# UWB_5V-3V3_LDO.net
KiCad netlist of a schematic drawn in Altium Designer
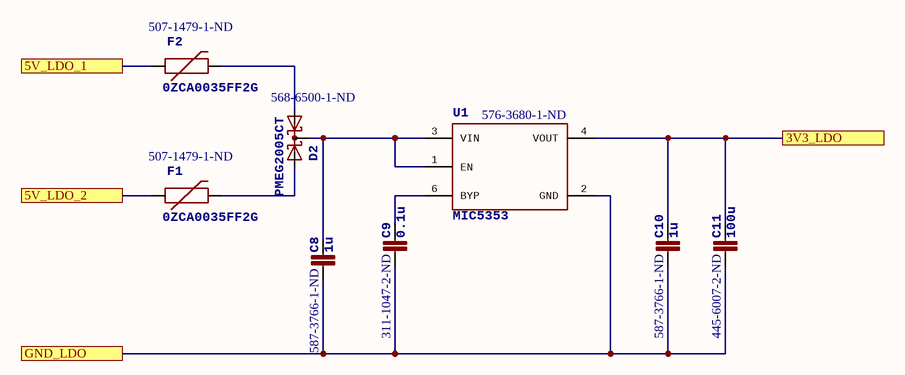
[diagram p0: UWB_5V-3V3_LDO.SchDoc]

(export (version "E")
  (design (tool "Eeschema 10.0.6"))
  (components
    (comp (ref "C8")
      (value "1u")
      (footprint "0603-CAP")
      (fields
        (field (name "PARTNO") "LMK107B7105KA-T")
        (field (name "SUPPLIER PART NUMBER 1") "587-3766-1-ND")
      )
      (libsource (lib "altium-import") (part "root_0_CAPACITOR-0603_"))
    )
    (comp (ref "C9")
      (value "0.1u")
      (footprint "0402-CAP")
      (fields
        (field (name "PARTNO") "LMK105BJ104KV-F")
        (field (name "SUPPLIER PART NUMBER 1") "311-1047-2-ND")
      )
      (libsource (lib "altium-import") (part "root_0_CAPACITOR-0402_"))
    )
    (comp (ref "C10")
      (value "1u")
      (footprint "0603-CAP")
      (fields
        (field (name "PARTNO") "LMK107B7105KA-T")
        (field (name "SUPPLIER PART NUMBER 1") "587-3766-1-ND")
      )
      (libsource (lib "altium-import") (part "root_0_CAPACITOR-0603_"))
    )
    (comp (ref "C11")
      (value "100u")
      (footprint "1206-CAP")
      (fields
        (field (name "PARTNO") "C3216X5R1A107M160AC")
        (field (name "SUPPLIER PART NUMBER 1") "445-6007-2-ND")
      )
      (libsource (lib "altium-import") (part "root_0_CAPACITOR-1206_"))
    )
    (comp (ref "D2")
      (value "PMEG2005CT")
      (footprint "SOT23-3")
      (description "DIODE SCHOTTKY 20V 500MA TO236AB")
      (fields (field (name "SUPPLIER PART NUMBER 1") "568-6500-1-ND"))
      (libsource (lib "pixhawk2") (part "PMEG2005CT"))
    )
    (comp (ref "F1")
      (value "0ZCA0035FF2G")
      (footprint "PTC-1206")
      (description "PTC RESTTBLE 0.35A 16V CHIP 1206")
      (fields (field (name "SUPPLIER PART NUMBER 1") "507-1479-1-ND"))
      (libsource (lib "pixhawk2") (part "PTCSMD"))
    )
    (comp (ref "F2")
      (value "0ZCA0035FF2G")
      (footprint "PTC-1206")
      (description "PTC RESTTBLE 0.35A 16V CHIP 1206")
      (fields (field (name "SUPPLIER PART NUMBER 1") "507-1479-1-ND"))
      (libsource (lib "pixhawk2") (part "PTCSMD"))
    )
    (comp (ref "U1")
      (value "MIC5353")
      (footprint "MLF-6-1.6MM")
      (fields (field (name "SUPPLIER PART NUMBER 1") "576-3680-1-ND"))
      (libsource (lib "altium-import") (part "root_0_MIC5353_"))
    )
  )
  (nets
    (net (code "1") (name "/3V3_LDO") (class "Default")
      (node (ref "C10") (pin "1") (pinfunction "1_1") (pintype "passive"))
      (node (ref "C11") (pin "1") (pinfunction "1_1") (pintype "passive"))
      (node (ref "U1") (pin "4") (pinfunction "VOUT_4") (pintype "passive"))
    )
    (net (code "2") (name "/5V_LDO_1") (class "Default")
      (node (ref "F2") (pin "1") (pinfunction "1_1") (pintype "passive"))
    )
    (net (code "3") (name "/5V_LDO_2") (class "Default")
      (node (ref "F1") (pin "1") (pinfunction "1_1") (pintype "passive"))
    )
    (net (code "4") (name "/GND_LDO") (class "Default")
      (node (ref "C10") (pin "2") (pinfunction "2_2") (pintype "passive"))
      (node (ref "C11") (pin "2") (pinfunction "2_2") (pintype "passive"))
      (node (ref "C8") (pin "2") (pinfunction "2_2") (pintype "passive"))
      (node (ref "C9") (pin "2") (pinfunction "2_2") (pintype "passive"))
      (node (ref "U1") (pin "2") (pinfunction "GND_2") (pintype "passive"))
    )
    (net (code "5") (name "Net-(D2-A1)") (class "Default")
      (node (ref "D2") (pin "1") (pinfunction "A1_1") (pintype "passive"))
      (node (ref "F2") (pin "2") (pinfunction "2_2") (pintype "passive"))
    )
    (net (code "6") (name "Net-(D2-A2)") (class "Default")
      (node (ref "D2") (pin "2") (pinfunction "A2_2") (pintype "passive"))
      (node (ref "F1") (pin "2") (pinfunction "2_2") (pintype "passive"))
    )
    (net (code "7") (name "Net-(D2-CC)") (class "Default")
      (node (ref "C8") (pin "1") (pinfunction "1_1") (pintype "passive"))
      (node (ref "D2") (pin "3") (pinfunction "CC_3") (pintype "passive"))
      (node (ref "U1") (pin "1") (pinfunction "EN_1") (pintype "passive"))
      (node (ref "U1") (pin "3") (pinfunction "VIN_3") (pintype "passive"))
    )
    (net (code "8") (name "Net-(U1-BYP)") (class "Default")
      (node (ref "C9") (pin "1") (pinfunction "1_1") (pintype "passive"))
      (node (ref "U1") (pin "6") (pinfunction "BYP_6") (pintype "passive"))
    )
  )
)
